# Filter_Capacitors_-_IoT_UART.net
KiCad netlist of a schematic drawn in Altium Designer
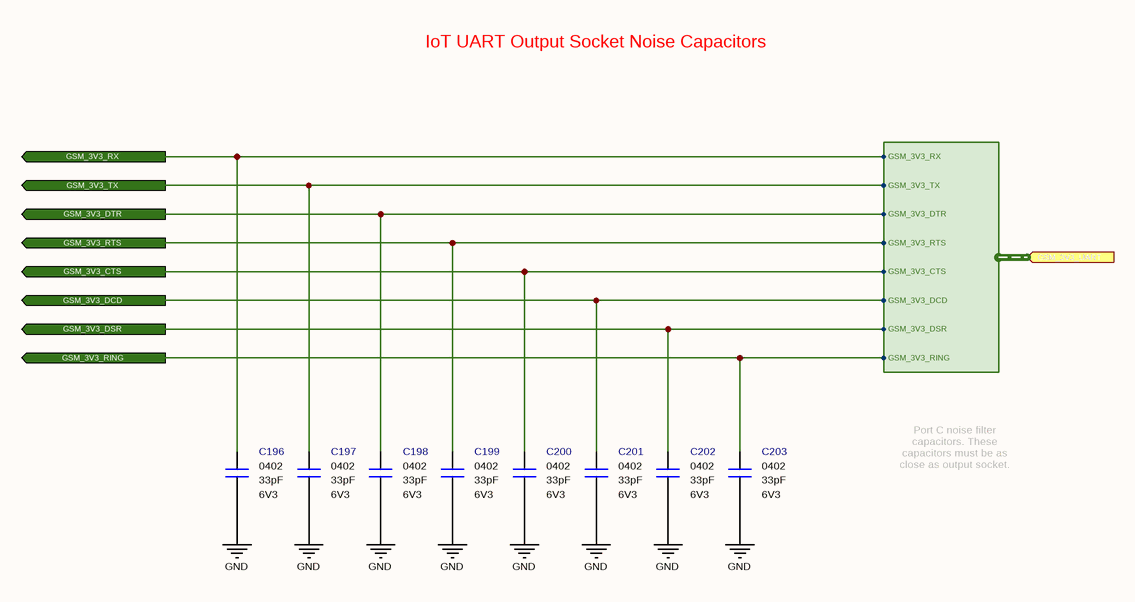
[diagram p0: Filter Capacitors - IoT UART.SchDoc]

(export (version "E")
  (design (tool "Eeschema 10.0.6"))
  (components
    (comp (ref "C196")
      (value "33pF")
      (footprint "CAPACITOR_0402")
      (description "Capacitor - 33pF [0402] (Ceramic)")
      (fields
        (field (name "TOLERANCE") "10%")
        (field (name "CASE") "0402")
        (field (name "VOLTAGE") "6V3")
        (field (name "MANUFACTURER PART NUMBER") "C0402C330J9RACAUTO")
      )
      (libsource (lib "Ovoo_Library") (part "Capacitor - 33pF [0402-6V3]"))
    )
    (comp (ref "C197")
      (value "33pF")
      (footprint "CAPACITOR_0402")
      (description "Capacitor - 33pF [0402] (Ceramic)")
      (fields
        (field (name "TOLERANCE") "10%")
        (field (name "CASE") "0402")
        (field (name "VOLTAGE") "6V3")
        (field (name "MANUFACTURER PART NUMBER") "C0402C330J9RACAUTO")
      )
      (libsource (lib "Ovoo_Library") (part "Capacitor - 33pF [0402-6V3]"))
    )
    (comp (ref "C198")
      (value "33pF")
      (footprint "CAPACITOR_0402")
      (description "Capacitor - 33pF [0402] (Ceramic)")
      (fields
        (field (name "TOLERANCE") "10%")
        (field (name "CASE") "0402")
        (field (name "VOLTAGE") "6V3")
        (field (name "MANUFACTURER PART NUMBER") "C0402C330J9RACAUTO")
      )
      (libsource (lib "Ovoo_Library") (part "Capacitor - 33pF [0402-6V3]"))
    )
    (comp (ref "C199")
      (value "33pF")
      (footprint "CAPACITOR_0402")
      (description "Capacitor - 33pF [0402] (Ceramic)")
      (fields
        (field (name "TOLERANCE") "10%")
        (field (name "CASE") "0402")
        (field (name "VOLTAGE") "6V3")
        (field (name "MANUFACTURER PART NUMBER") "C0402C330J9RACAUTO")
      )
      (libsource (lib "Ovoo_Library") (part "Capacitor - 33pF [0402-6V3]"))
    )
    (comp (ref "C200")
      (value "33pF")
      (footprint "CAPACITOR_0402")
      (description "Capacitor - 33pF [0402] (Ceramic)")
      (fields
        (field (name "TOLERANCE") "10%")
        (field (name "CASE") "0402")
        (field (name "VOLTAGE") "6V3")
        (field (name "MANUFACTURER PART NUMBER") "C0402C330J9RACAUTO")
      )
      (libsource (lib "Ovoo_Library") (part "Capacitor - 33pF [0402-6V3]"))
    )
    (comp (ref "C201")
      (value "33pF")
      (footprint "CAPACITOR_0402")
      (description "Capacitor - 33pF [0402] (Ceramic)")
      (fields
        (field (name "TOLERANCE") "10%")
        (field (name "CASE") "0402")
        (field (name "VOLTAGE") "6V3")
        (field (name "MANUFACTURER PART NUMBER") "C0402C330J9RACAUTO")
      )
      (libsource (lib "Ovoo_Library") (part "Capacitor - 33pF [0402-6V3]"))
    )
    (comp (ref "C202")
      (value "33pF")
      (footprint "CAPACITOR_0402")
      (description "Capacitor - 33pF [0402] (Ceramic)")
      (fields
        (field (name "TOLERANCE") "10%")
        (field (name "CASE") "0402")
        (field (name "VOLTAGE") "6V3")
        (field (name "MANUFACTURER PART NUMBER") "C0402C330J9RACAUTO")
      )
      (libsource (lib "Ovoo_Library") (part "Capacitor - 33pF [0402-6V3]"))
    )
    (comp (ref "C203")
      (value "33pF")
      (footprint "CAPACITOR_0402")
      (description "Capacitor - 33pF [0402] (Ceramic)")
      (fields
        (field (name "TOLERANCE") "10%")
        (field (name "CASE") "0402")
        (field (name "VOLTAGE") "6V3")
        (field (name "MANUFACTURER PART NUMBER") "C0402C330J9RACAUTO")
      )
      (libsource (lib "Ovoo_Library") (part "Capacitor - 33pF [0402-6V3]"))
    )
  )
  (nets
    (net (code "2") (name "/GSM_3V3_CTS") (class "Default")
      (node (ref "C200") (pin "2") (pinfunction "2_2") (pintype "passive"))
    )
    (net (code "3") (name "/GSM_3V3_DCD") (class "Default")
      (node (ref "C201") (pin "2") (pinfunction "2_2") (pintype "passive"))
    )
    (net (code "4") (name "/GSM_3V3_DSR") (class "Default")
      (node (ref "C202") (pin "2") (pinfunction "2_2") (pintype "passive"))
    )
    (net (code "5") (name "/GSM_3V3_DTR") (class "Default")
      (node (ref "C198") (pin "2") (pinfunction "2_2") (pintype "passive"))
    )
    (net (code "6") (name "/GSM_3V3_RING") (class "Default")
      (node (ref "C203") (pin "2") (pinfunction "2_2") (pintype "passive"))
    )
    (net (code "7") (name "/GSM_3V3_RTS") (class "Default")
      (node (ref "C199") (pin "2") (pinfunction "2_2") (pintype "passive"))
    )
    (net (code "8") (name "/GSM_3V3_RX") (class "Default")
      (node (ref "C196") (pin "2") (pinfunction "2_2") (pintype "passive"))
    )
    (net (code "9") (name "/GSM_3V3_TX") (class "Default")
      (node (ref "C197") (pin "2") (pinfunction "2_2") (pintype "passive"))
    )
    (net (code "11") (name "GND") (class "Default")
      (node (ref "C196") (pin "1") (pinfunction "1_1") (pintype "passive"))
      (node (ref "C197") (pin "1") (pinfunction "1_1") (pintype "passive"))
      (node (ref "C198") (pin "1") (pinfunction "1_1") (pintype "passive"))
      (node (ref "C199") (pin "1") (pinfunction "1_1") (pintype "passive"))
      (node (ref "C200") (pin "1") (pinfunction "1_1") (pintype "passive"))
      (node (ref "C201") (pin "1") (pinfunction "1_1") (pintype "passive"))
      (node (ref "C202") (pin "1") (pinfunction "1_1") (pintype "passive"))
      (node (ref "C203") (pin "1") (pinfunction "1_1") (pintype "passive"))
    )
  )
)
